# hackeeg-connector-8-horizontal.net
KiCad netlist of a schematic drawn in EAGLE
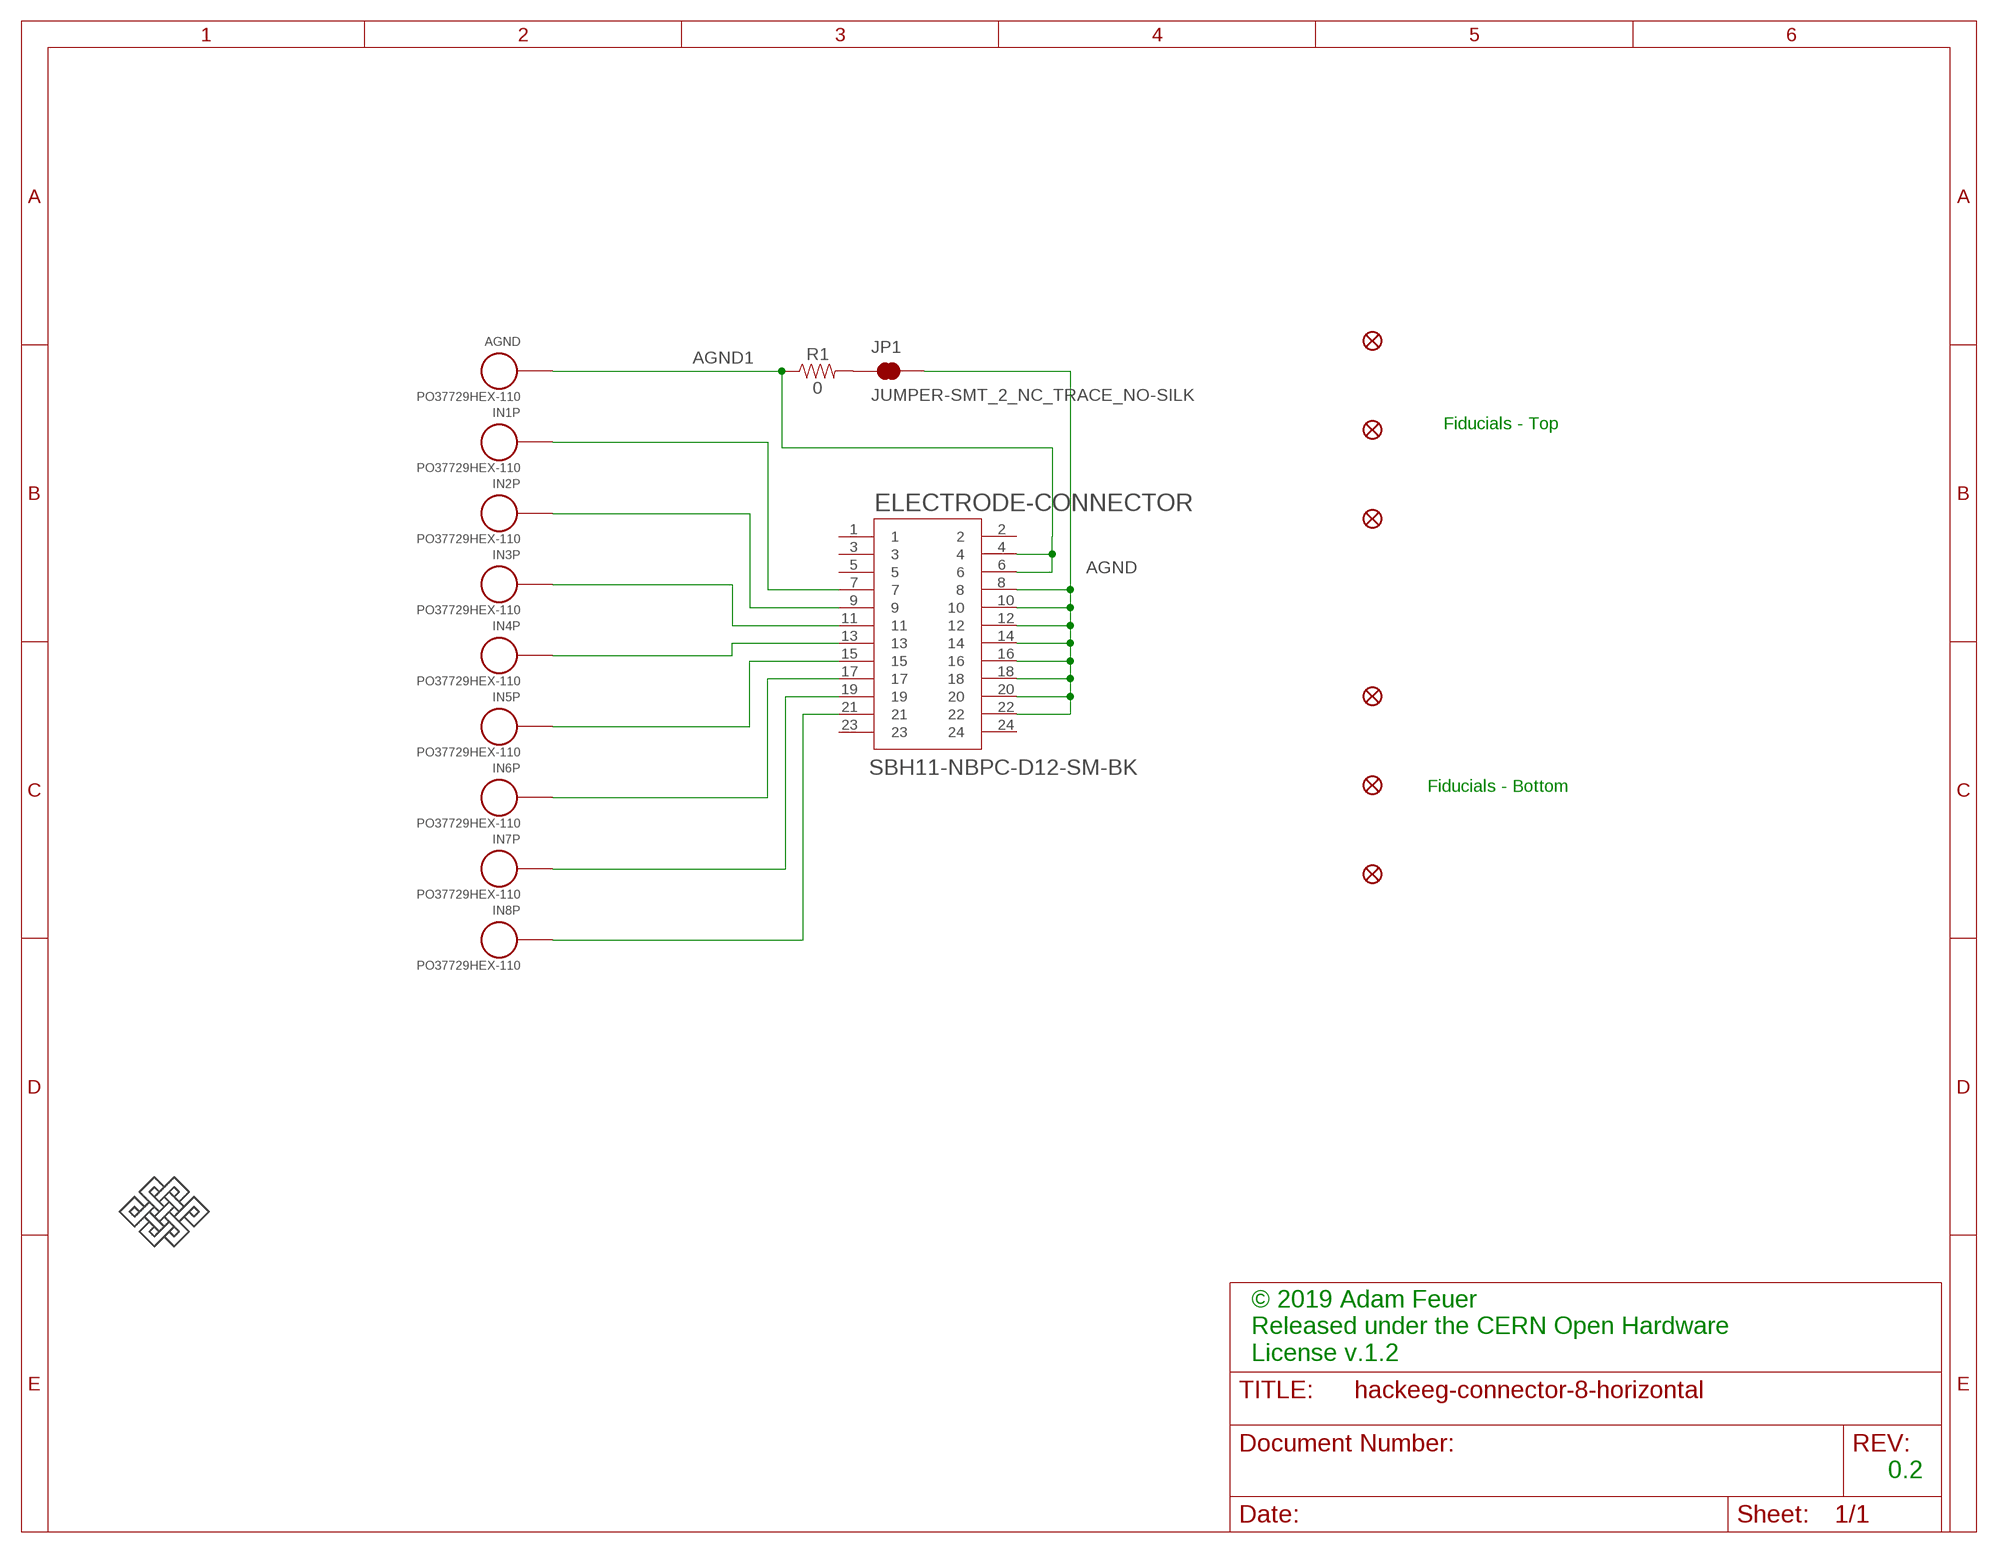
[diagram p0: schematic, sheet 1]

(export (version "E")
  (design (tool "Eeschema 10.0.6"))
  (components
    (comp (ref "AGND")
      (value "PO37729HEX-110")
      (footprint "eagle-import:HEX-110")
      (libsource (lib "eagle-import") (part "PO37729HEX-110"))
    )
    (comp (ref "ELECTRODE-CONNECTOR")
      (value "SBH11-NBPC-D12-SM-BK")
      (footprint "eagle-import:SULLINS_SBH11-NBPC-D12-SM-BK")
      (fields (field (name "MF") "Sullins Connector"))
      (libsource (lib "eagle-import") (part "SBH11-NBPC-D12-SM-BK"))
    )
    (comp (ref "FD1")
      (value "FIDUCIAL1X2")
      (footprint "eagle-import:FIDUCIAL-1X2")
      (libsource (lib "eagle-import") (part "FIDUCIAL1X2"))
    )
    (comp (ref "FD2")
      (value "FIDUCIAL1X2")
      (footprint "eagle-import:FIDUCIAL-1X2")
      (libsource (lib "eagle-import") (part "FIDUCIAL1X2"))
    )
    (comp (ref "FD3")
      (value "FIDUCIAL1X2")
      (footprint "eagle-import:FIDUCIAL-1X2")
      (libsource (lib "eagle-import") (part "FIDUCIAL1X2"))
    )
    (comp (ref "FD4")
      (value "FIDUCIAL1X2")
      (footprint "eagle-import:FIDUCIAL-1X2")
      (libsource (lib "eagle-import") (part "FIDUCIAL1X2"))
    )
    (comp (ref "FD5")
      (value "FIDUCIAL1X2")
      (footprint "eagle-import:FIDUCIAL-1X2")
      (libsource (lib "eagle-import") (part "FIDUCIAL1X2"))
    )
    (comp (ref "FD6")
      (value "FIDUCIAL1X2")
      (footprint "eagle-import:FIDUCIAL-1X2")
      (libsource (lib "eagle-import") (part "FIDUCIAL1X2"))
    )
    (comp (ref "IN1P")
      (value "PO37729HEX-110")
      (footprint "eagle-import:HEX-110")
      (libsource (lib "eagle-import") (part "PO37729HEX-110"))
    )
    (comp (ref "IN2P")
      (value "PO37729HEX-110")
      (footprint "eagle-import:HEX-110")
      (libsource (lib "eagle-import") (part "PO37729HEX-110"))
    )
    (comp (ref "IN3P")
      (value "PO37729HEX-110")
      (footprint "eagle-import:HEX-110")
      (libsource (lib "eagle-import") (part "PO37729HEX-110"))
    )
    (comp (ref "IN4P")
      (value "PO37729HEX-110")
      (footprint "eagle-import:HEX-110")
      (libsource (lib "eagle-import") (part "PO37729HEX-110"))
    )
    (comp (ref "IN5P")
      (value "PO37729HEX-110")
      (footprint "eagle-import:HEX-110")
      (libsource (lib "eagle-import") (part "PO37729HEX-110"))
    )
    (comp (ref "IN6P")
      (value "PO37729HEX-110")
      (footprint "eagle-import:HEX-110")
      (libsource (lib "eagle-import") (part "PO37729HEX-110"))
    )
    (comp (ref "IN7P")
      (value "PO37729HEX-110")
      (footprint "eagle-import:HEX-110")
      (libsource (lib "eagle-import") (part "PO37729HEX-110"))
    )
    (comp (ref "IN8P")
      (value "PO37729HEX-110")
      (footprint "eagle-import:HEX-110")
      (libsource (lib "eagle-import") (part "PO37729HEX-110"))
    )
    (comp (ref "JP1")
      (value "JUMPER-SMT_2_NC_TRACE_NO-SILK")
      (footprint "eagle-import:SMT-JUMPER_2_NC_TRACE_NO-SILK")
      (libsource (lib "eagle-import") (part "JUMPER-SMT_2_NC_TRACE_NO-SILK"))
    )
    (comp (ref "R1")
      (value "0")
      (footprint "eagle-import:0603")
      (libsource (lib "eagle-import") (part "0OHM-0603-1/10W-5%"))
    )
    (comp (ref "U$1")
      (value "ENDLESSKNOTENDLESSKNOT-MEDIUM")
      (footprint "eagle-import:ENDLESSKNOT-MEDIUM")
      (libsource (lib "eagle-import") (part "ENDLESSKNOTENDLESSKNOT-MEDIUM"))
    )
  )
  (nets
    (net (code "1") (name "/AGND") (class "Default")
      (node (ref "ELECTRODE-CONNECTOR") (pin "10") (pinfunction "10_10") (pintype "passive"))
      (node (ref "ELECTRODE-CONNECTOR") (pin "12") (pinfunction "12_12") (pintype "passive"))
      (node (ref "ELECTRODE-CONNECTOR") (pin "14") (pinfunction "14_14") (pintype "passive"))
      (node (ref "ELECTRODE-CONNECTOR") (pin "16") (pinfunction "16_16") (pintype "passive"))
      (node (ref "ELECTRODE-CONNECTOR") (pin "18") (pinfunction "18_18") (pintype "passive"))
      (node (ref "ELECTRODE-CONNECTOR") (pin "20") (pinfunction "20_20") (pintype "passive"))
      (node (ref "ELECTRODE-CONNECTOR") (pin "22") (pinfunction "22_22") (pintype "passive"))
      (node (ref "ELECTRODE-CONNECTOR") (pin "8") (pinfunction "8_8") (pintype "passive"))
      (node (ref "JP1") (pin "2") (pinfunction "2_2") (pintype "passive"))
    )
    (net (code "2") (name "/AGND1") (class "Default")
      (node (ref "AGND") (pin "SIGNAL") (pinfunction "SIGNAL_SIGNAL") (pintype "bidirectional"))
      (node (ref "ELECTRODE-CONNECTOR") (pin "4") (pinfunction "4_4") (pintype "passive"))
      (node (ref "ELECTRODE-CONNECTOR") (pin "6") (pinfunction "6_6") (pintype "passive"))
      (node (ref "R1") (pin "1") (pinfunction "1_1") (pintype "passive"))
    )
    (net (code "3") (name "Net-(ELECTRODE-CONNECTOR-Pad7)") (class "Default")
      (node (ref "ELECTRODE-CONNECTOR") (pin "7") (pinfunction "7_7") (pintype "passive"))
      (node (ref "IN1P") (pin "SIGNAL") (pinfunction "SIGNAL_SIGNAL") (pintype "bidirectional"))
    )
    (net (code "4") (name "Net-(ELECTRODE-CONNECTOR-Pad9)") (class "Default")
      (node (ref "ELECTRODE-CONNECTOR") (pin "9") (pinfunction "9_9") (pintype "passive"))
      (node (ref "IN2P") (pin "SIGNAL") (pinfunction "SIGNAL_SIGNAL") (pintype "bidirectional"))
    )
    (net (code "5") (name "Net-(ELECTRODE-CONNECTOR-Pad11)") (class "Default")
      (node (ref "ELECTRODE-CONNECTOR") (pin "11") (pinfunction "11_11") (pintype "passive"))
      (node (ref "IN3P") (pin "SIGNAL") (pinfunction "SIGNAL_SIGNAL") (pintype "bidirectional"))
    )
    (net (code "6") (name "Net-(ELECTRODE-CONNECTOR-Pad13)") (class "Default")
      (node (ref "ELECTRODE-CONNECTOR") (pin "13") (pinfunction "13_13") (pintype "passive"))
      (node (ref "IN4P") (pin "SIGNAL") (pinfunction "SIGNAL_SIGNAL") (pintype "bidirectional"))
    )
    (net (code "7") (name "Net-(ELECTRODE-CONNECTOR-Pad15)") (class "Default")
      (node (ref "ELECTRODE-CONNECTOR") (pin "15") (pinfunction "15_15") (pintype "passive"))
      (node (ref "IN5P") (pin "SIGNAL") (pinfunction "SIGNAL_SIGNAL") (pintype "bidirectional"))
    )
    (net (code "8") (name "Net-(ELECTRODE-CONNECTOR-Pad17)") (class "Default")
      (node (ref "ELECTRODE-CONNECTOR") (pin "17") (pinfunction "17_17") (pintype "passive"))
      (node (ref "IN6P") (pin "SIGNAL") (pinfunction "SIGNAL_SIGNAL") (pintype "bidirectional"))
    )
    (net (code "9") (name "Net-(ELECTRODE-CONNECTOR-Pad19)") (class "Default")
      (node (ref "ELECTRODE-CONNECTOR") (pin "19") (pinfunction "19_19") (pintype "passive"))
      (node (ref "IN7P") (pin "SIGNAL") (pinfunction "SIGNAL_SIGNAL") (pintype "bidirectional"))
    )
    (net (code "10") (name "Net-(ELECTRODE-CONNECTOR-Pad21)") (class "Default")
      (node (ref "ELECTRODE-CONNECTOR") (pin "21") (pinfunction "21_21") (pintype "passive"))
      (node (ref "IN8P") (pin "SIGNAL") (pinfunction "SIGNAL_SIGNAL") (pintype "bidirectional"))
    )
    (net (code "11") (name "Net-(JP1-Pad1)") (class "Default")
      (node (ref "JP1") (pin "1") (pinfunction "1_1") (pintype "passive"))
      (node (ref "R1") (pin "2") (pinfunction "2_2") (pintype "passive"))
    )
    (net (code "12") (name "unconnected-(ELECTRODE-CONNECTOR-Pad1)") (class "Default")
      (node (ref "ELECTRODE-CONNECTOR") (pin "1") (pinfunction "1_1") (pintype "passive"))
    )
    (net (code "13") (name "unconnected-(ELECTRODE-CONNECTOR-Pad2)") (class "Default")
      (node (ref "ELECTRODE-CONNECTOR") (pin "2") (pinfunction "2_2") (pintype "passive"))
    )
    (net (code "14") (name "unconnected-(ELECTRODE-CONNECTOR-Pad3)") (class "Default")
      (node (ref "ELECTRODE-CONNECTOR") (pin "3") (pinfunction "3_3") (pintype "passive"))
    )
    (net (code "15") (name "unconnected-(ELECTRODE-CONNECTOR-Pad5)") (class "Default")
      (node (ref "ELECTRODE-CONNECTOR") (pin "5") (pinfunction "5_5") (pintype "passive"))
    )
    (net (code "16") (name "unconnected-(ELECTRODE-CONNECTOR-Pad23)") (class "Default")
      (node (ref "ELECTRODE-CONNECTOR") (pin "23") (pinfunction "23_23") (pintype "passive"))
    )
    (net (code "17") (name "unconnected-(ELECTRODE-CONNECTOR-Pad24)") (class "Default")
      (node (ref "ELECTRODE-CONNECTOR") (pin "24") (pinfunction "24_24") (pintype "passive"))
    )
  )
)
